# Aegaeon_REV_C_PROTO.net
KiCad netlist of a schematic drawn in EAGLE
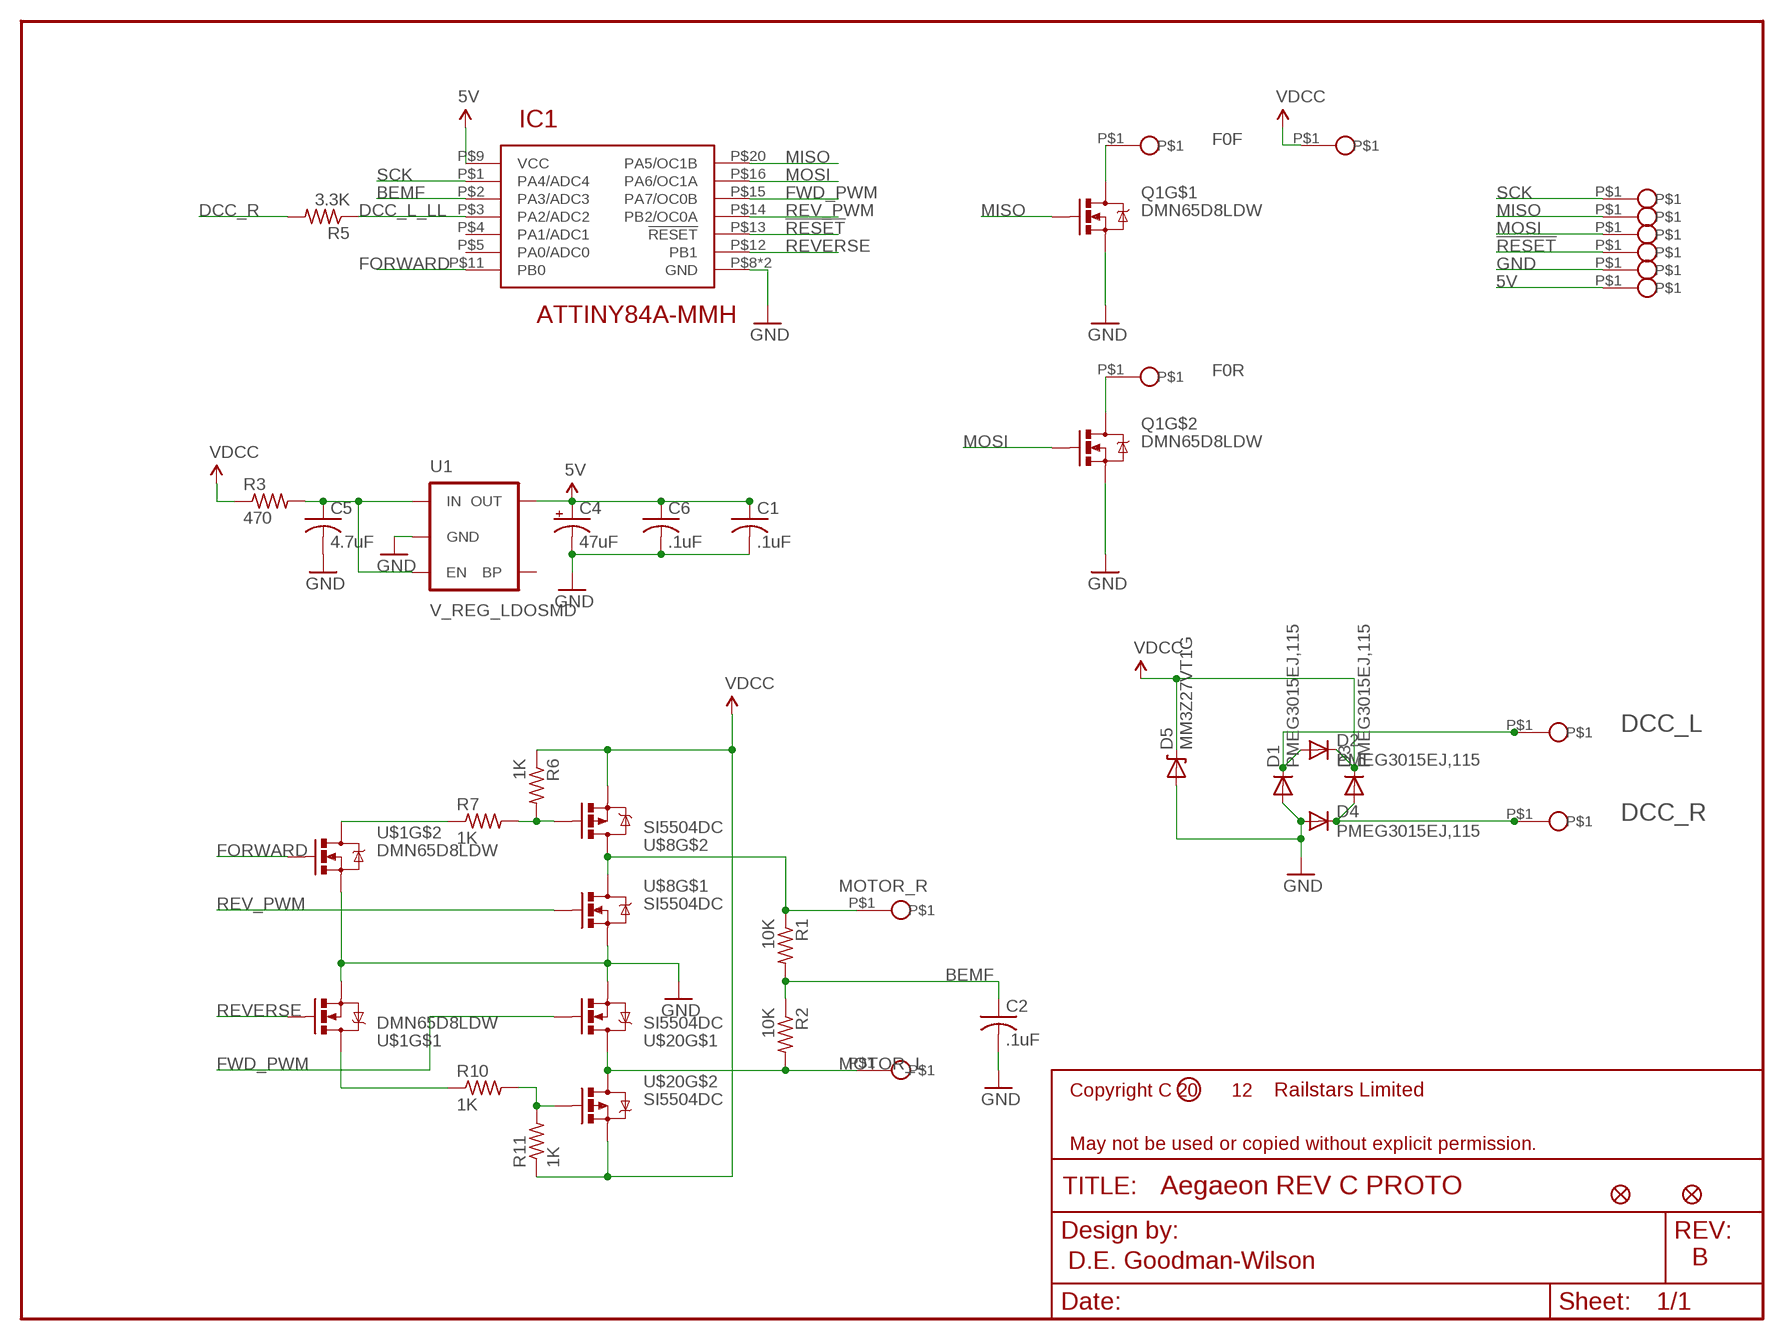
[diagram p0: schematic, sheet 1]

(export (version "E")
  (design (tool "Eeschema 10.0.6"))
  (components
    (comp (ref "C1")
      (value ".1uF")
      (footprint "eagle-import:C0201")
      (libsource (lib "eagle-import") (part "C-USC0201"))
    )
    (comp (ref "C2")
      (value ".1uF")
      (footprint "eagle-import:C0402")
      (libsource (lib "eagle-import") (part "C-USC0402"))
    )
    (comp (ref "C4")
      (value "47uF")
      (footprint "eagle-import:CPOL0603")
      (libsource (lib "eagle-import") (part "CPOL-USF980J476MMA"))
    )
    (comp (ref "C5")
      (value "4.7uF")
      (footprint "eagle-import:C0603")
      (libsource (lib "eagle-import") (part "C-USC0603"))
    )
    (comp (ref "C6")
      (value ".1uF")
      (footprint "eagle-import:C0402")
      (libsource (lib "eagle-import") (part "C-USC0402"))
    )
    (comp (ref "D1")
      (value "PMEG3015EJ,115")
      (footprint "eagle-import:SOD-323")
      (libsource (lib "eagle-import") (part "DIODESOD"))
    )
    (comp (ref "D2")
      (value "PMEG3015EJ,115")
      (footprint "eagle-import:SOD-323")
      (libsource (lib "eagle-import") (part "DIODESOD"))
    )
    (comp (ref "D3")
      (value "PMEG3015EJ,115")
      (footprint "eagle-import:SOD-323")
      (libsource (lib "eagle-import") (part "DIODESOD"))
    )
    (comp (ref "D4")
      (value "PMEG3015EJ,115")
      (footprint "eagle-import:SOD-323")
      (libsource (lib "eagle-import") (part "DIODESOD"))
    )
    (comp (ref "D5")
      (value "MM3Z27VT1G")
      (footprint "eagle-import:SOD-323")
      (libsource (lib "eagle-import") (part "DIODE-ZENER-BZT52"))
    )
    (comp (ref "DCC_L")
      (value "PAD1MM")
      (footprint "eagle-import:LED_SOLDER_PAD")
      (libsource (lib "eagle-import") (part "PAD1MM"))
    )
    (comp (ref "DCC_R")
      (value "PAD1MM")
      (footprint "eagle-import:LED_SOLDER_PAD")
      (libsource (lib "eagle-import") (part "PAD1MM"))
    )
    (comp (ref "IC1")
      (value "ATTINY84A-MMH")
      (footprint "eagle-import:VQFN-20")
      (libsource (lib "eagle-import") (part "ATTINY84A-MMH"))
    )
    (comp (ref "JP2")
      (value "FIDUCIALUFIDUCIAL")
      (footprint "eagle-import:MICRO-FIDUCIAL")
      (libsource (lib "eagle-import") (part "FIDUCIALUFIDUCIAL"))
    )
    (comp (ref "JP4")
      (value "FIDUCIALUFIDUCIAL")
      (footprint "eagle-import:MICRO-FIDUCIAL")
      (libsource (lib "eagle-import") (part "FIDUCIALUFIDUCIAL"))
    )
    (comp (ref "Q1")
      (value "DMN65D8LDW")
      (footprint "eagle-import:SOT363")
      (libsource (lib "eagle-import") (part "DMN65D8LDW"))
    )
    (comp (ref "R1")
      (value "10K")
      (footprint "eagle-import:R0201")
      (libsource (lib "eagle-import") (part "R-US_R0201"))
    )
    (comp (ref "R2")
      (value "10K")
      (footprint "eagle-import:R0201")
      (libsource (lib "eagle-import") (part "R-US_R0201"))
    )
    (comp (ref "R3")
      (value "470")
      (footprint "eagle-import:R0201")
      (libsource (lib "eagle-import") (part "R-US_R0201"))
    )
    (comp (ref "R5")
      (value "3.3K")
      (footprint "eagle-import:R0201")
      (libsource (lib "eagle-import") (part "R-US_R0201"))
    )
    (comp (ref "R6")
      (value "1K")
      (footprint "eagle-import:R0201")
      (libsource (lib "eagle-import") (part "R-US_R0201"))
    )
    (comp (ref "R7")
      (value "1K")
      (footprint "eagle-import:R0201")
      (libsource (lib "eagle-import") (part "R-US_R0201"))
    )
    (comp (ref "R10")
      (value "1K")
      (footprint "eagle-import:R0201")
      (libsource (lib "eagle-import") (part "R-US_R0201"))
    )
    (comp (ref "R11")
      (value "1K")
      (footprint "eagle-import:R0201")
      (libsource (lib "eagle-import") (part "R-US_R0201"))
    )
    (comp (ref "U$1")
      (value "DMN65D8LDW")
      (footprint "eagle-import:SOT363")
      (libsource (lib "eagle-import") (part "DMN65D8LDW"))
    )
    (comp (ref "U$2")
      (value "PAD1MM")
      (footprint "eagle-import:LED_SOLDER_PAD")
      (libsource (lib "eagle-import") (part "PAD1MM"))
    )
    (comp (ref "U$3")
      (value "PAD1MM")
      (footprint "eagle-import:LED_SOLDER_PAD")
      (libsource (lib "eagle-import") (part "PAD1MM"))
    )
    (comp (ref "U$5")
      (value "PAD1MM")
      (footprint "eagle-import:LED_SOLDER_PAD")
      (libsource (lib "eagle-import") (part "PAD1MM"))
    )
    (comp (ref "U$8")
      (value "SI5504DC")
      (footprint "eagle-import:1206-8")
      (libsource (lib "eagle-import") (part "SI5504DC"))
    )
    (comp (ref "U$10")
      (value "PAD1MM")
      (footprint "eagle-import:LED_SOLDER_PAD")
      (libsource (lib "eagle-import") (part "PAD1MM"))
    )
    (comp (ref "U$11")
      (value "PAD1MM")
      (footprint "eagle-import:LED_SOLDER_PAD")
      (libsource (lib "eagle-import") (part "PAD1MM"))
    )
    (comp (ref "U$14")
      (value "PAD.75MM")
      (footprint "eagle-import:POGO_PAD")
      (libsource (lib "eagle-import") (part "PAD.75MM"))
    )
    (comp (ref "U$15")
      (value "PAD.75MM")
      (footprint "eagle-import:POGO_PAD")
      (libsource (lib "eagle-import") (part "PAD.75MM"))
    )
    (comp (ref "U$16")
      (value "PAD.75MM")
      (footprint "eagle-import:POGO_PAD")
      (libsource (lib "eagle-import") (part "PAD.75MM"))
    )
    (comp (ref "U$17")
      (value "PAD.75MM")
      (footprint "eagle-import:POGO_PAD")
      (libsource (lib "eagle-import") (part "PAD.75MM"))
    )
    (comp (ref "U$18")
      (value "PAD.75MM")
      (footprint "eagle-import:POGO_PAD")
      (libsource (lib "eagle-import") (part "PAD.75MM"))
    )
    (comp (ref "U$19")
      (value "PAD.75MM")
      (footprint "eagle-import:POGO_PAD")
      (libsource (lib "eagle-import") (part "PAD.75MM"))
    )
    (comp (ref "U$20")
      (value "SI5504DC")
      (footprint "eagle-import:1206-8")
      (libsource (lib "eagle-import") (part "SI5504DC"))
    )
    (comp (ref "U1")
      (value "V_REG_LDOSMD")
      (footprint "eagle-import:SOT23-5")
      (libsource (lib "eagle-import") (part "V_REG_LDOSMD"))
    )
  )
  (nets
    (net (code "1") (name "/BEMF") (class "Default")
      (node (ref "C2") (pin "1") (pinfunction "1_1") (pintype "passive"))
      (node (ref "IC1") (pin "P$2") (pinfunction "PA3/ADC3_P$2") (pintype "bidirectional"))
      (node (ref "R1") (pin "2") (pinfunction "2_2") (pintype "passive"))
      (node (ref "R2") (pin "1") (pinfunction "1_1") (pintype "passive"))
    )
    (net (code "2") (name "/DCC_L") (class "Default")
      (node (ref "D1") (pin "1") (pinfunction "C_1") (pintype "passive"))
      (node (ref "D2") (pin "2") (pinfunction "A_2") (pintype "passive"))
      (node (ref "DCC_L") (pin "P$1") (pinfunction "P$1_P$1") (pintype "bidirectional"))
    )
    (net (code "3") (name "/DCC_L_LL") (class "Default")
      (node (ref "IC1") (pin "P$3") (pinfunction "PA2/ADC2_P$3") (pintype "bidirectional"))
      (node (ref "R5") (pin "1") (pinfunction "1_1") (pintype "passive"))
    )
    (net (code "4") (name "/DCC_R") (class "Default")
      (node (ref "D3") (pin "2") (pinfunction "A_2") (pintype "passive"))
      (node (ref "D4") (pin "1") (pinfunction "C_1") (pintype "passive"))
      (node (ref "DCC_R") (pin "P$1") (pinfunction "P$1_P$1") (pintype "bidirectional"))
      (node (ref "R5") (pin "2") (pinfunction "2_2") (pintype "passive"))
    )
    (net (code "5") (name "/F0F") (class "Default")
      (node (ref "Q1") (pin "P$4") (pinfunction "D_P$4") (pintype "passive"))
      (node (ref "U$10") (pin "P$1") (pinfunction "P$1_P$1") (pintype "bidirectional"))
    )
    (net (code "6") (name "/F0R") (class "Default")
      (node (ref "Q1") (pin "P$1") (pinfunction "D_P$1") (pintype "passive"))
      (node (ref "U$5") (pin "P$1") (pinfunction "P$1_P$1") (pintype "bidirectional"))
    )
    (net (code "7") (name "/FORWARD") (class "Default")
      (node (ref "IC1") (pin "P$11") (pinfunction "PB0_P$11") (pintype "bidirectional"))
      (node (ref "U$1") (pin "P$5") (pinfunction "G_P$5") (pintype "passive"))
    )
    (net (code "8") (name "/FWD_PWM") (class "Default")
      (node (ref "IC1") (pin "P$15") (pinfunction "PA7/OC0B_P$15") (pintype "bidirectional"))
      (node (ref "U$20") (pin "P$2") (pinfunction "G_P$2") (pintype "passive"))
    )
    (net (code "9") (name "/MISO") (class "Default")
      (node (ref "IC1") (pin "P$20") (pinfunction "PA5/OC1B_P$20") (pintype "bidirectional"))
      (node (ref "Q1") (pin "P$2") (pinfunction "G_P$2") (pintype "passive"))
      (node (ref "U$15") (pin "P$1") (pinfunction "P$1_P$1") (pintype "bidirectional"))
    )
    (net (code "10") (name "/MOSI") (class "Default")
      (node (ref "IC1") (pin "P$16") (pinfunction "PA6/OC1A_P$16") (pintype "bidirectional"))
      (node (ref "Q1") (pin "P$5") (pinfunction "G_P$5") (pintype "passive"))
      (node (ref "U$16") (pin "P$1") (pinfunction "P$1_P$1") (pintype "bidirectional"))
    )
    (net (code "11") (name "/MOTOR_L") (class "Default")
      (node (ref "R2") (pin "2") (pinfunction "2_2") (pintype "passive"))
      (node (ref "U$20") (pin "P$5") (pinfunction "D_P$5") (pintype "passive"))
      (node (ref "U$20") (pin "P$6") (pinfunction "D_P$6") (pintype "passive"))
      (node (ref "U$20") (pin "P$7") (pinfunction "D_P$7") (pintype "passive"))
      (node (ref "U$20") (pin "P$8") (pinfunction "D_P$8") (pintype "passive"))
      (node (ref "U$3") (pin "P$1") (pinfunction "P$1_P$1") (pintype "bidirectional"))
    )
    (net (code "12") (name "/MOTOR_R") (class "Default")
      (node (ref "R1") (pin "1") (pinfunction "1_1") (pintype "passive"))
      (node (ref "U$2") (pin "P$1") (pinfunction "P$1_P$1") (pintype "bidirectional"))
      (node (ref "U$8") (pin "P$5") (pinfunction "D_P$5") (pintype "passive"))
      (node (ref "U$8") (pin "P$6") (pinfunction "D_P$6") (pintype "passive"))
      (node (ref "U$8") (pin "P$7") (pinfunction "D_P$7") (pintype "passive"))
      (node (ref "U$8") (pin "P$8") (pinfunction "D_P$8") (pintype "passive"))
    )
    (net (code "13") (name "/REVERSE") (class "Default")
      (node (ref "IC1") (pin "P$12") (pinfunction "PB1_P$12") (pintype "bidirectional"))
      (node (ref "U$1") (pin "P$2") (pinfunction "G_P$2") (pintype "passive"))
    )
    (net (code "14") (name "/REV_PWM") (class "Default")
      (node (ref "IC1") (pin "P$14") (pinfunction "PB2/OC0A_P$14") (pintype "bidirectional"))
      (node (ref "U$8") (pin "P$2") (pinfunction "G_P$2") (pintype "passive"))
    )
    (net (code "15") (name "/SCK") (class "Default")
      (node (ref "IC1") (pin "P$1") (pinfunction "PA4/ADC4_P$1") (pintype "bidirectional"))
      (node (ref "U$14") (pin "P$1") (pinfunction "P$1_P$1") (pintype "bidirectional"))
    )
    (net (code "16") (name "/~{RESET}") (class "Default")
      (node (ref "IC1") (pin "P$13") (pinfunction "~{RESET}_P$13") (pintype "bidirectional"))
      (node (ref "U$17") (pin "P$1") (pinfunction "P$1_P$1") (pintype "bidirectional"))
    )
    (net (code "17") (name "5V") (class "Default")
      (node (ref "C1") (pin "1") (pinfunction "1_1") (pintype "passive"))
      (node (ref "C4") (pin "1") (pinfunction "+_1") (pintype "passive"))
      (node (ref "C6") (pin "1") (pinfunction "1_1") (pintype "passive"))
      (node (ref "IC1") (pin "P$9") (pinfunction "VCC_P$9") (pintype "bidirectional"))
      (node (ref "U$19") (pin "P$1") (pinfunction "P$1_P$1") (pintype "bidirectional"))
      (node (ref "U1") (pin "5") (pinfunction "OUT_5") (pintype "passive"))
    )
    (net (code "18") (name "GND") (class "Default")
      (node (ref "C1") (pin "2") (pinfunction "2_2") (pintype "passive"))
      (node (ref "C2") (pin "2") (pinfunction "2_2") (pintype "passive"))
      (node (ref "C4") (pin "2") (pinfunction "-_2") (pintype "passive"))
      (node (ref "C5") (pin "2") (pinfunction "2_2") (pintype "passive"))
      (node (ref "C6") (pin "2") (pinfunction "2_2") (pintype "passive"))
      (node (ref "D1") (pin "2") (pinfunction "A_2") (pintype "passive"))
      (node (ref "D4") (pin "2") (pinfunction "A_2") (pintype "passive"))
      (node (ref "D5") (pin "2") (pinfunction "A_2") (pintype "passive"))
      (node (ref "IC1") (pin "P$21") (pinfunction "GND_P$21") (pintype "bidirectional"))
      (node (ref "IC1") (pin "P$8") (pinfunction "GND_P$8") (pintype "bidirectional"))
      (node (ref "Q1") (pin "P$3") (pinfunction "S_P$3") (pintype "passive"))
      (node (ref "Q1") (pin "P$6") (pinfunction "S_P$6") (pintype "passive"))
      (node (ref "U$1") (pin "P$3") (pinfunction "S_P$3") (pintype "passive"))
      (node (ref "U$1") (pin "P$6") (pinfunction "S_P$6") (pintype "passive"))
      (node (ref "U$18") (pin "P$1") (pinfunction "P$1_P$1") (pintype "bidirectional"))
      (node (ref "U$20") (pin "P$1") (pinfunction "S_P$1") (pintype "passive"))
      (node (ref "U$8") (pin "P$1") (pinfunction "S_P$1") (pintype "passive"))
      (node (ref "U1") (pin "2") (pinfunction "GND_2") (pintype "input"))
    )
    (net (code "19") (name "Net-(U$1A-D)") (class "Default")
      (node (ref "R10") (pin "1") (pinfunction "1_1") (pintype "passive"))
      (node (ref "U$1") (pin "P$4") (pinfunction "D_P$4") (pintype "passive"))
    )
    (net (code "20") (name "Net-(U$1B-D)") (class "Default")
      (node (ref "R7") (pin "1") (pinfunction "1_1") (pintype "passive"))
      (node (ref "U$1") (pin "P$1") (pinfunction "D_P$1") (pintype "passive"))
    )
    (net (code "21") (name "Net-(U$8B-G)") (class "Default")
      (node (ref "R6") (pin "2") (pinfunction "2_2") (pintype "passive"))
      (node (ref "R7") (pin "2") (pinfunction "2_2") (pintype "passive"))
      (node (ref "U$8") (pin "P$4") (pinfunction "G_P$4") (pintype "passive"))
    )
    (net (code "22") (name "Net-(U$20B-G)") (class "Default")
      (node (ref "R10") (pin "2") (pinfunction "2_2") (pintype "passive"))
      (node (ref "R11") (pin "2") (pinfunction "2_2") (pintype "passive"))
      (node (ref "U$20") (pin "P$4") (pinfunction "G_P$4") (pintype "passive"))
    )
    (net (code "23") (name "Net-(U1-EN)") (class "Default")
      (node (ref "C5") (pin "1") (pinfunction "1_1") (pintype "passive"))
      (node (ref "R3") (pin "2") (pinfunction "2_2") (pintype "passive"))
      (node (ref "U1") (pin "1") (pinfunction "IN_1") (pintype "input"))
      (node (ref "U1") (pin "3") (pinfunction "EN_3") (pintype "input"))
    )
    (net (code "24") (name "VDCC") (class "Default")
      (node (ref "D2") (pin "1") (pinfunction "C_1") (pintype "passive"))
      (node (ref "D3") (pin "1") (pinfunction "C_1") (pintype "passive"))
      (node (ref "D5") (pin "1") (pinfunction "C_1") (pintype "passive"))
      (node (ref "R11") (pin "1") (pinfunction "1_1") (pintype "passive"))
      (node (ref "R3") (pin "1") (pinfunction "1_1") (pintype "passive"))
      (node (ref "R6") (pin "1") (pinfunction "1_1") (pintype "passive"))
      (node (ref "U$11") (pin "P$1") (pinfunction "P$1_P$1") (pintype "bidirectional"))
      (node (ref "U$20") (pin "P$3") (pinfunction "S_P$3") (pintype "passive"))
      (node (ref "U$8") (pin "P$3") (pinfunction "S_P$3") (pintype "passive"))
    )
    (net (code "25") (name "unconnected-(IC1-PA0{slash}ADC0-PadP$5)") (class "Default")
      (node (ref "IC1") (pin "P$5") (pinfunction "PA0/ADC0_P$5") (pintype "bidirectional"))
    )
    (net (code "26") (name "unconnected-(IC1-PA1{slash}ADC1-PadP$4)") (class "Default")
      (node (ref "IC1") (pin "P$4") (pinfunction "PA1/ADC1_P$4") (pintype "bidirectional"))
    )
    (net (code "27") (name "unconnected-(U1-BP-Pad4)") (class "Default")
      (node (ref "U1") (pin "4") (pinfunction "BP_4") (pintype "input"))
    )
  )
)
